# Power.net
KiCad netlist of a schematic drawn in Altium Designer
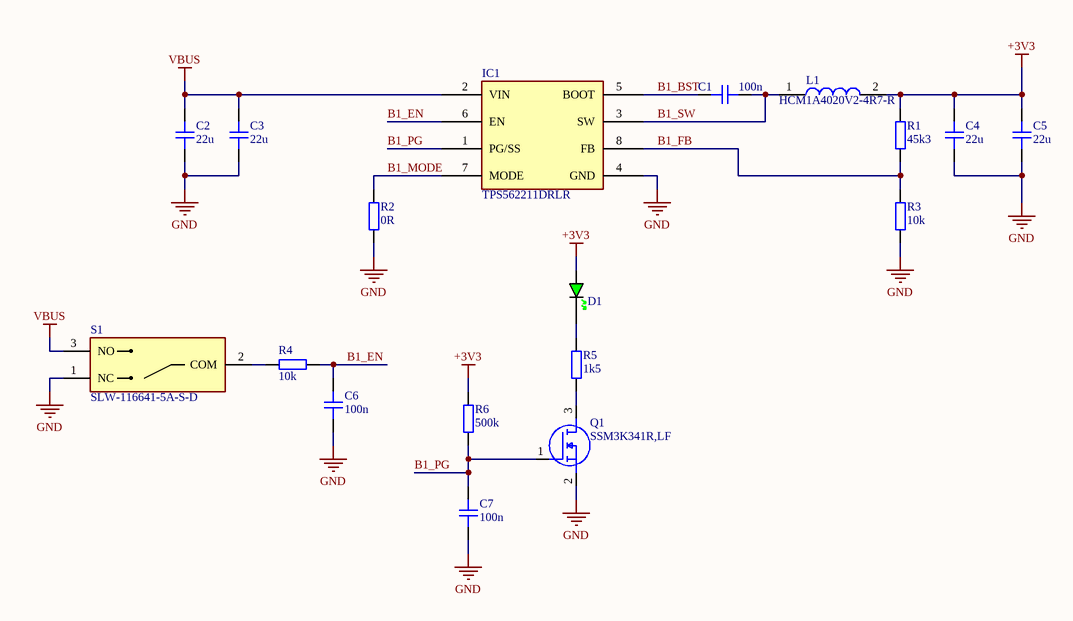
[diagram p0: Power.SchDoc]

(export (version "E")
  (design (tool "Eeschema 10.0.6"))
  (components
    (comp (ref "C1")
      (value "100n")
      (footprint "CAP_0402")
      (description "Capacitor SMD 0402")
      (libsource (lib "Schematic-Lib-PhilsLab") (part "CAP_0402"))
    )
    (comp (ref "C2")
      (value "22u")
      (footprint "CAP_0603")
      (description "Capacitor SMD 0603")
      (libsource (lib "Schematic-Lib-PhilsLab") (part "CAP_0603"))
    )
    (comp (ref "C3")
      (value "22u")
      (footprint "CAP_0603")
      (description "Capacitor SMD 0603")
      (libsource (lib "Schematic-Lib-PhilsLab") (part "CAP_0603"))
    )
    (comp (ref "C4")
      (value "22u")
      (footprint "CAP_0603")
      (description "Capacitor SMD 0603")
      (libsource (lib "Schematic-Lib-PhilsLab") (part "CAP_0603"))
    )
    (comp (ref "C5")
      (value "22u")
      (footprint "CAP_0603")
      (description "Capacitor SMD 0603")
      (libsource (lib "Schematic-Lib-PhilsLab") (part "CAP_0603"))
    )
    (comp (ref "C6")
      (value "100n")
      (footprint "CAP_0402")
      (description "Capacitor SMD 0402")
      (libsource (lib "Schematic-Lib-PhilsLab") (part "CAP_0402"))
    )
    (comp (ref "C7")
      (value "100n")
      (footprint "CAP_0402")
      (description "Capacitor SMD 0402")
      (libsource (lib "Schematic-Lib-PhilsLab") (part "CAP_0402"))
    )
    (comp (ref "D1")
      (value "GREEN")
      (footprint "LED_0603_GREEN")
      (description "LED 0603 GREEN SMD")
      (libsource (lib "Schematic-Lib-PhilsLab") (part "LED_0603_GREEN"))
    )
    (comp (ref "IC1")
      (value "TPS562211DRLR")
      (footprint "Footprint-Lib-PhilsLab:SOTFL50P160X60-8N")
      (description "Integrated Circuit")
      (fields (field (name "MOUSER PART NUMBER") "595-TPS562211DRLR"))
      (libsource (lib "Schematic-Lib-PhilsLab") (part "TPS562211DRLR"))
    )
    (comp (ref "L1")
      (value "HCM1A4020V2-4R7-R")
      (footprint "Footprint-Lib-PhilsLab:INDPM4442X200N")
      (description "Inductor")
      (fields (field (name "MOUSER PART NUMBER") "504-HCM1A4020V24R7-R"))
      (libsource (lib "Schematic-Lib-PhilsLab") (part "HCM1A4020V2-4R7-R"))
    )
    (comp (ref "Q1")
      (value "SSM3K341R,LF")
      (footprint "Footprint-Lib-PhilsLab:SOTFL95P240X88-3N")
      (description "MOSFET (N-Channel)")
      (fields (field (name "MOUSER PART NUMBER") "757-SSM3K341RLF"))
      (libsource (lib "Schematic-Lib-PhilsLab") (part "SSM3K341R,LF"))
    )
    (comp (ref "R1")
      (value "45k3")
      (footprint "RES_0402")
      (description "Resistor SMD 0402")
      (libsource (lib "Schematic-Lib-PhilsLab") (part "RES_0402"))
    )
    (comp (ref "R2")
      (value "0R")
      (footprint "RES_0402")
      (description "Resistor SMD 0402")
      (libsource (lib "Schematic-Lib-PhilsLab") (part "RES_0402"))
    )
    (comp (ref "R3")
      (value "10k")
      (footprint "RES_0402")
      (description "Resistor SMD 0402")
      (libsource (lib "Schematic-Lib-PhilsLab") (part "RES_0402"))
    )
    (comp (ref "R4")
      (value "10k")
      (footprint "RES_0402")
      (description "Resistor SMD 0402")
      (libsource (lib "Schematic-Lib-PhilsLab") (part "RES_0402"))
    )
    (comp (ref "R5")
      (value "1k5")
      (footprint "RES_0603")
      (description "Resistor SMD 0603")
      (libsource (lib "Schematic-Lib-PhilsLab") (part "RES_0603"))
    )
    (comp (ref "R6")
      (value "500k")
      (footprint "RES_0402")
      (description "Resistor SMD 0402")
      (libsource (lib "Schematic-Lib-PhilsLab") (part "RES_0402"))
    )
    (comp (ref "S1")
      (value "SLW-116641-5A-S-D")
      (footprint "Footprint-Lib-PhilsLab:SLW1166415ASD")
      (description "Switch")
      (fields (field (name "MOUSER PART NUMBER") "179-SLW1166415ASD"))
      (libsource (lib "Schematic-Lib-PhilsLab") (part "SLW-116641-5A-S-D"))
    )
  )
  (nets
    (net (code "1") (name "+3V3") (class "Default")
      (node (ref "C4") (pin "2") (pinfunction "2_2") (pintype "passive"))
      (node (ref "C5") (pin "2") (pinfunction "2_2") (pintype "passive"))
      (node (ref "D1") (pin "A") (pinfunction "A_A") (pintype "passive"))
      (node (ref "L1") (pin "2") (pinfunction "2_2") (pintype "passive"))
      (node (ref "R1") (pin "2") (pinfunction "2_2") (pintype "passive"))
      (node (ref "R6") (pin "2") (pinfunction "2_2") (pintype "passive"))
    )
    (net (code "2") (name "/B1_BST") (class "Default")
      (node (ref "C1") (pin "2") (pinfunction "2_2") (pintype "passive"))
      (node (ref "IC1") (pin "5") (pinfunction "BOOT_5") (pintype "passive"))
    )
    (net (code "3") (name "/B1_EN") (class "Default")
      (node (ref "C6") (pin "1") (pinfunction "1_1") (pintype "passive"))
      (node (ref "IC1") (pin "6") (pinfunction "EN_6") (pintype "passive"))
      (node (ref "R4") (pin "1") (pinfunction "1_1") (pintype "passive"))
    )
    (net (code "4") (name "/B1_FB") (class "Default")
      (node (ref "IC1") (pin "8") (pinfunction "FB_8") (pintype "passive"))
      (node (ref "R1") (pin "1") (pinfunction "1_1") (pintype "passive"))
      (node (ref "R3") (pin "2") (pinfunction "2_2") (pintype "passive"))
    )
    (net (code "5") (name "/B1_MODE") (class "Default")
      (node (ref "IC1") (pin "7") (pinfunction "MODE_7") (pintype "passive"))
      (node (ref "R2") (pin "2") (pinfunction "2_2") (pintype "passive"))
    )
    (net (code "6") (name "/B1_PG") (class "Default")
      (node (ref "C7") (pin "1") (pinfunction "1_1") (pintype "passive"))
      (node (ref "IC1") (pin "1") (pinfunction "PG/SS_1") (pintype "passive"))
      (node (ref "Q1") (pin "1") (pinfunction "G_1") (pintype "passive"))
      (node (ref "R6") (pin "1") (pinfunction "1_1") (pintype "passive"))
    )
    (net (code "7") (name "/B1_SW") (class "Default")
      (node (ref "C1") (pin "1") (pinfunction "1_1") (pintype "passive"))
      (node (ref "IC1") (pin "3") (pinfunction "SW_3") (pintype "passive"))
      (node (ref "L1") (pin "1") (pinfunction "1_1") (pintype "passive"))
    )
    (net (code "8") (name "GND") (class "Default")
      (node (ref "C2") (pin "1") (pinfunction "1_1") (pintype "passive"))
      (node (ref "C3") (pin "1") (pinfunction "1_1") (pintype "passive"))
      (node (ref "C4") (pin "1") (pinfunction "1_1") (pintype "passive"))
      (node (ref "C5") (pin "1") (pinfunction "1_1") (pintype "passive"))
      (node (ref "C6") (pin "2") (pinfunction "2_2") (pintype "passive"))
      (node (ref "C7") (pin "2") (pinfunction "2_2") (pintype "passive"))
      (node (ref "IC1") (pin "4") (pinfunction "GND_4") (pintype "passive"))
      (node (ref "Q1") (pin "2") (pinfunction "S_2") (pintype "passive"))
      (node (ref "R2") (pin "1") (pinfunction "1_1") (pintype "passive"))
      (node (ref "R3") (pin "1") (pinfunction "1_1") (pintype "passive"))
      (node (ref "S1") (pin "1") (pinfunction "NC_1") (pintype "passive"))
    )
    (net (code "9") (name "Net-(D1-PadK)") (class "Default")
      (node (ref "D1") (pin "K") (pinfunction "K_K") (pintype "passive"))
      (node (ref "R5") (pin "2") (pinfunction "2_2") (pintype "passive"))
    )
    (net (code "10") (name "Net-(Q1-D)") (class "Default")
      (node (ref "Q1") (pin "3") (pinfunction "D_3") (pintype "passive"))
      (node (ref "R5") (pin "1") (pinfunction "1_1") (pintype "passive"))
    )
    (net (code "11") (name "Net-(S1-COM)") (class "Default")
      (node (ref "R4") (pin "2") (pinfunction "2_2") (pintype "passive"))
      (node (ref "S1") (pin "2") (pinfunction "COM_2") (pintype "passive"))
    )
    (net (code "12") (name "VBUS") (class "Default")
      (node (ref "C2") (pin "2") (pinfunction "2_2") (pintype "passive"))
      (node (ref "C3") (pin "2") (pinfunction "2_2") (pintype "passive"))
      (node (ref "IC1") (pin "2") (pinfunction "VIN_2") (pintype "passive"))
      (node (ref "S1") (pin "3") (pinfunction "NO_3") (pintype "passive"))
    )
  )
)
